# LB_BIT_iX_1IN_1OUT-XLWIDE-v03_1_1x.net
KiCad netlist of a schematic drawn in EAGLE
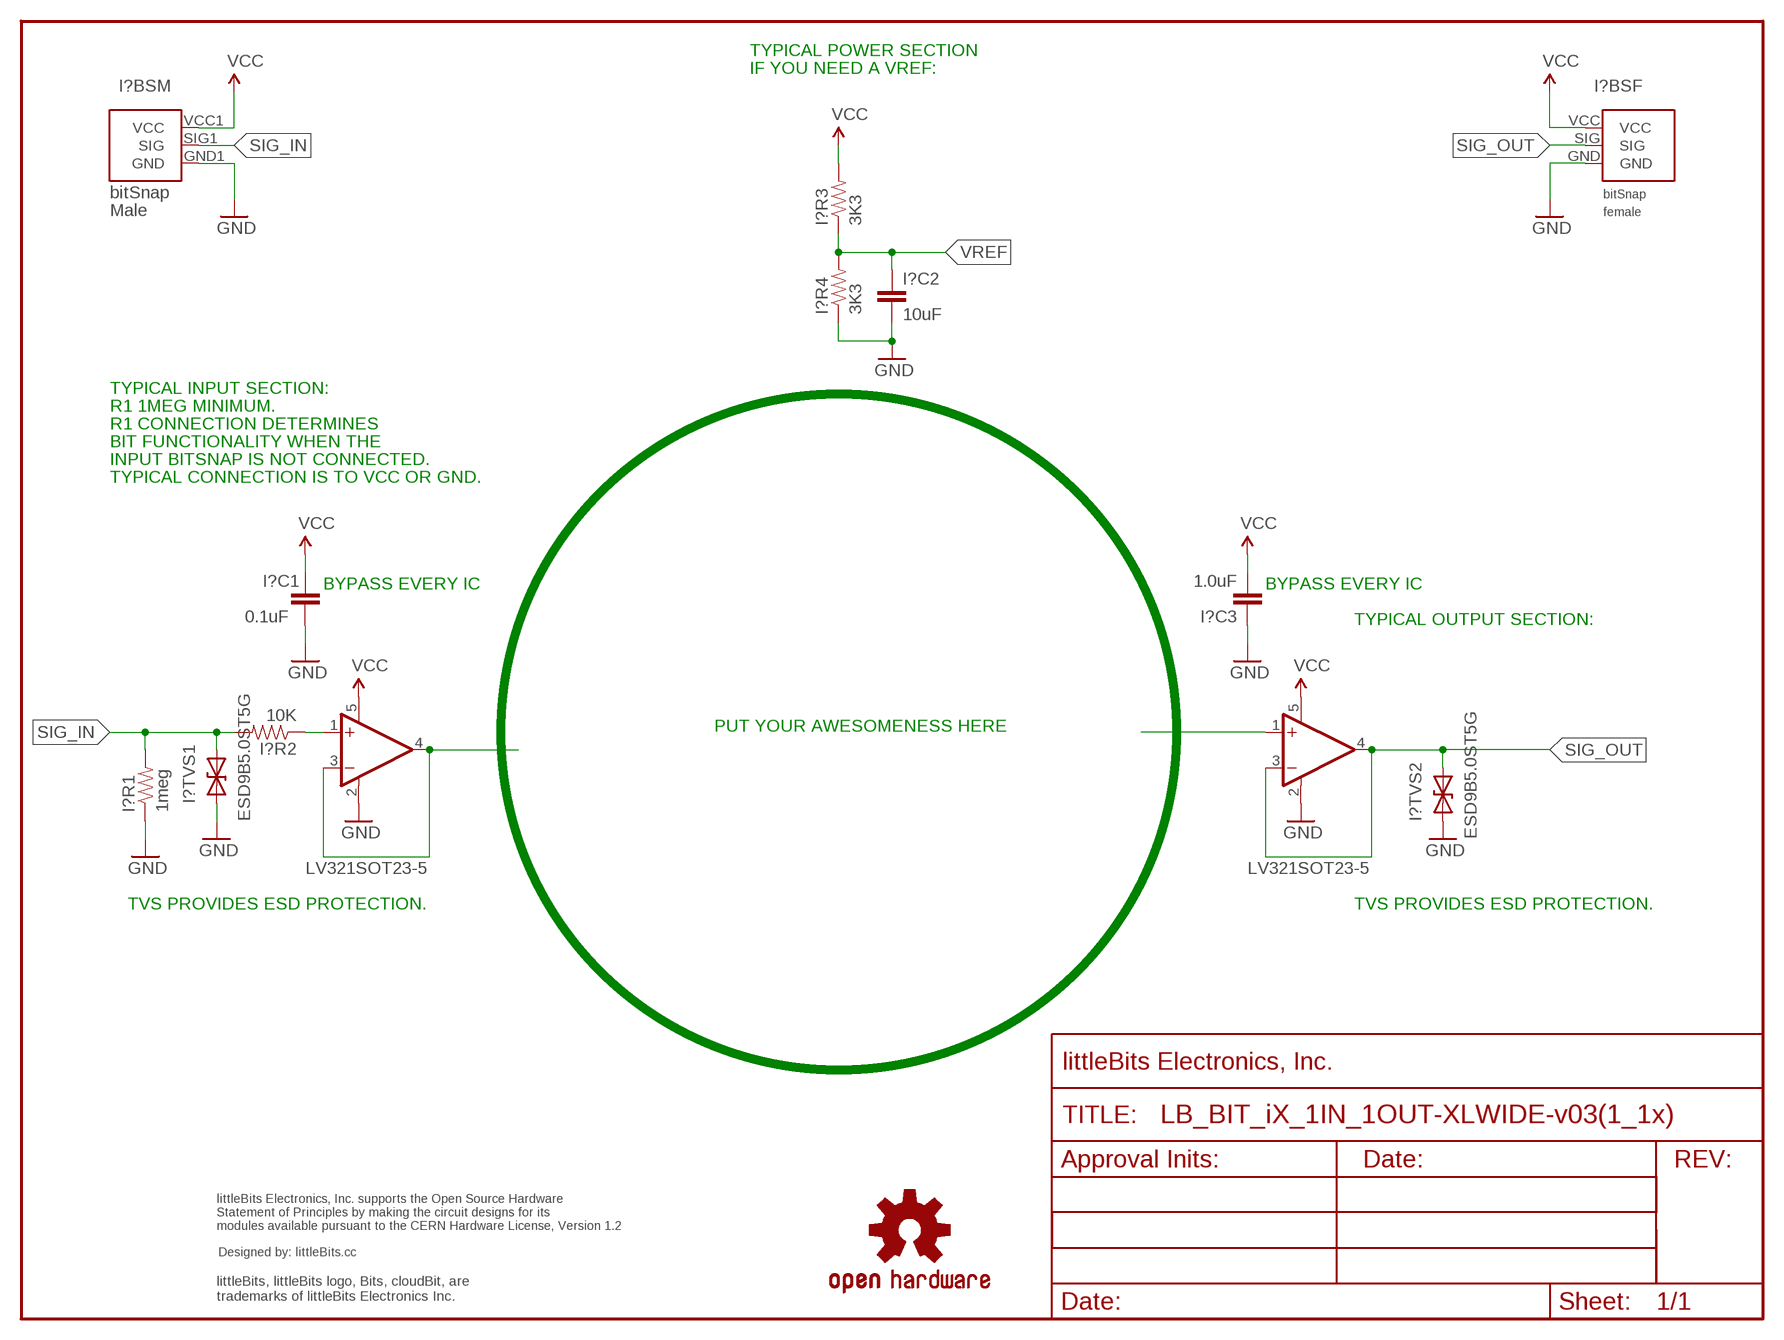
[diagram p0: schematic, sheet 1]

(export (version "E")
  (design (tool "Eeschema 10.0.6"))
  (components
    (comp (ref "I?BSF")
      (value "BITSNAP_V03_FEMALE")
      (footprint "eagle-import:BITSNAP_V03_FEMALE")
      (libsource (lib "eagle-import") (part "BITSNAP_V03_FEMALE"))
    )
    (comp (ref "I?BSM")
      (value "BITSNAP_V03_MALE")
      (footprint "eagle-import:BITSNAP_V03_MALE")
      (libsource (lib "eagle-import") (part "BITSNAP_V03_MALE"))
    )
    (comp (ref "I?C1")
      (value "0.1uF")
      (footprint "eagle-import:CAP-0603")
      (libsource (lib "eagle-import") (part "CAPCAP-0603"))
    )
    (comp (ref "I?C2")
      (value "10uF")
      (footprint "eagle-import:CAP-0603")
      (libsource (lib "eagle-import") (part "CAPCAP-0603"))
    )
    (comp (ref "I?C3")
      (value "1.0uF")
      (footprint "eagle-import:CAP-0603")
      (libsource (lib "eagle-import") (part "CAPCAP-0603"))
    )
    (comp (ref "I?R1")
      (value "1meg")
      (footprint "eagle-import:RES-0603")
      (libsource (lib "eagle-import") (part "RESISTOR0603"))
    )
    (comp (ref "I?R2")
      (value "10K")
      (footprint "eagle-import:RES-0603")
      (libsource (lib "eagle-import") (part "RESISTOR0603"))
    )
    (comp (ref "I?R3")
      (value "3K3")
      (footprint "eagle-import:RES-0603")
      (libsource (lib "eagle-import") (part "RESISTOR0603"))
    )
    (comp (ref "I?R4")
      (value "3K3")
      (footprint "eagle-import:RES-0603")
      (libsource (lib "eagle-import") (part "RESISTOR0603"))
    )
    (comp (ref "I?TVS1")
      (value "ESD9B5.0ST5G")
      (footprint "eagle-import:SOD-923")
      (libsource (lib "eagle-import") (part "DIODE-TVSSOD-923"))
    )
    (comp (ref "I?TVS2")
      (value "ESD9B5.0ST5G")
      (footprint "eagle-import:SOD-923")
      (libsource (lib "eagle-import") (part "DIODE-TVSSOD-923"))
    )
    (comp (ref "U$1")
      (value "OSHWCREDIT")
      (footprint "eagle-import:OSHWCREDIT")
      (libsource (lib "eagle-import") (part "OSHWCREDIT"))
    )
    (comp (ref "U$2")
      (value "OSHW-LOGOL")
      (footprint "eagle-import:OSHW-LOGO-L")
      (libsource (lib "eagle-import") (part "OSHW-LOGOL"))
    )
    (comp (ref "U$5")
      (value "FRAME-LETTER")
      (footprint "eagle-import:FABDWG01-OHW")
      (libsource (lib "eagle-import") (part "FRAME-LETTER"))
    )
    (comp (ref "U1")
      (value "LV321SOT23-5")
      (footprint "eagle-import:SOT23-5")
      (libsource (lib "eagle-import") (part "LV321SOT23-5"))
    )
    (comp (ref "U2")
      (value "LV321SOT23-5")
      (footprint "eagle-import:SOT23-5")
      (libsource (lib "eagle-import") (part "LV321SOT23-5"))
    )
  )
  (nets
    (net (code "1") (name "GND") (class "Default")
      (node (ref "I?BSF") (pin "GND") (pinfunction "GND_GND") (pintype "bidirectional"))
      (node (ref "I?BSM") (pin "GND1") (pinfunction "GND_GND1") (pintype "bidirectional"))
      (node (ref "I?C1") (pin "2") (pinfunction "2_2") (pintype "passive"))
      (node (ref "I?C2") (pin "2") (pinfunction "2_2") (pintype "passive"))
      (node (ref "I?C3") (pin "1") (pinfunction "1_1") (pintype "passive"))
      (node (ref "I?R1") (pin "1") (pinfunction "1_1") (pintype "passive"))
      (node (ref "I?R4") (pin "1") (pinfunction "1_1") (pintype "passive"))
      (node (ref "I?TVS1") (pin "1") (pinfunction "A_1") (pintype "passive"))
      (node (ref "I?TVS2") (pin "1") (pinfunction "A_1") (pintype "passive"))
      (node (ref "U1") (pin "2") (pinfunction "V-_2") (pintype "power_in"))
      (node (ref "U2") (pin "2") (pinfunction "V-_2") (pintype "power_in"))
    )
    (net (code "2") (name "Net-(U1-+IN)") (class "Default")
      (node (ref "I?R2") (pin "1") (pinfunction "1_1") (pintype "passive"))
      (node (ref "U1") (pin "1") (pinfunction "+IN_1") (pintype "input"))
    )
    (net (code "3") (name "Net-(U1--IN)") (class "Default")
      (node (ref "U1") (pin "3") (pinfunction "-IN_3") (pintype "input"))
      (node (ref "U1") (pin "4") (pinfunction "OUT_4") (pintype "output"))
    )
    (net (code "4") (name "SIG_IN") (class "Default")
      (node (ref "I?BSM") (pin "SIG1") (pinfunction "SIG_SIG1") (pintype "bidirectional"))
      (node (ref "I?R1") (pin "2") (pinfunction "2_2") (pintype "passive"))
      (node (ref "I?R2") (pin "2") (pinfunction "2_2") (pintype "passive"))
      (node (ref "I?TVS1") (pin "2") (pinfunction "C_2") (pintype "passive"))
    )
    (net (code "5") (name "SIG_OUT") (class "Default")
      (node (ref "I?BSF") (pin "SIG") (pinfunction "SIG_SIG") (pintype "bidirectional"))
      (node (ref "I?TVS2") (pin "2") (pinfunction "C_2") (pintype "passive"))
      (node (ref "U2") (pin "3") (pinfunction "-IN_3") (pintype "input"))
      (node (ref "U2") (pin "4") (pinfunction "OUT_4") (pintype "output"))
    )
    (net (code "6") (name "VCC") (class "Default")
      (node (ref "I?BSF") (pin "VCC") (pinfunction "VCC_VCC") (pintype "bidirectional"))
      (node (ref "I?BSM") (pin "VCC1") (pinfunction "VCC_VCC1") (pintype "bidirectional"))
      (node (ref "I?C1") (pin "1") (pinfunction "1_1") (pintype "passive"))
      (node (ref "I?C3") (pin "2") (pinfunction "2_2") (pintype "passive"))
      (node (ref "I?R3") (pin "2") (pinfunction "2_2") (pintype "passive"))
      (node (ref "U1") (pin "5") (pinfunction "V+_5") (pintype "power_in"))
      (node (ref "U2") (pin "5") (pinfunction "V+_5") (pintype "power_in"))
    )
    (net (code "7") (name "VREF") (class "Default")
      (node (ref "I?C2") (pin "1") (pinfunction "1_1") (pintype "passive"))
      (node (ref "I?R3") (pin "1") (pinfunction "1_1") (pintype "passive"))
      (node (ref "I?R4") (pin "2") (pinfunction "2_2") (pintype "passive"))
    )
    (net (code "8") (name "unconnected-(U2-+IN-Pad1)") (class "Default")
      (node (ref "U2") (pin "1") (pinfunction "+IN_1") (pintype "input"))
    )
  )
)
